# uno.net
KiCad netlist of a schematic drawn in EAGLE
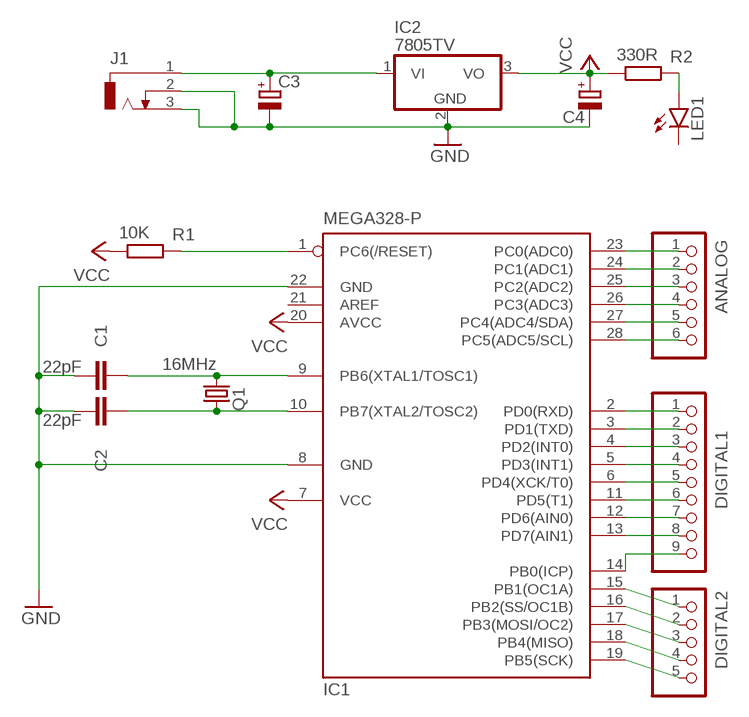
[diagram p0: schematic, sheet 1]

(export (version "E")
  (design (tool "Eeschema 10.0.6"))
  (components
    (comp (ref "ANALOG")
      (value "PINHD-1X6")
      (footprint "eagle-import:1X06")
      (libsource (lib "eagle-import") (part "PINHD-1X6"))
    )
    (comp (ref "C1")
      (value "22pF")
      (footprint "eagle-import:C025-024X044")
      (libsource (lib "eagle-import") (part "C-EU025-024X044"))
    )
    (comp (ref "C2")
      (value "22pF")
      (footprint "eagle-import:C025-024X044")
      (libsource (lib "eagle-import") (part "C-EU025-024X044"))
    )
    (comp (ref "C3")
      (value "CPOL-EUE2.5-6")
      (footprint "eagle-import:E2,5-6")
      (libsource (lib "eagle-import") (part "CPOL-EUE2.5-6"))
    )
    (comp (ref "C4")
      (value "CPOL-EUE2.5-6")
      (footprint "eagle-import:E2,5-6")
      (libsource (lib "eagle-import") (part "CPOL-EUE2.5-6"))
    )
    (comp (ref "DIGITAL1")
      (value "PINHD-1X9")
      (footprint "eagle-import:1X09")
      (libsource (lib "eagle-import") (part "PINHD-1X9"))
    )
    (comp (ref "DIGITAL2")
      (value "PINHD-1X5")
      (footprint "eagle-import:1X05")
      (libsource (lib "eagle-import") (part "PINHD-1X5"))
    )
    (comp (ref "IC1")
      (value "MEGA328-P")
      (footprint "eagle-import:DIL28-3")
      (libsource (lib "eagle-import") (part "MEGA8-P"))
    )
    (comp (ref "IC2")
      (value "7805TV")
      (footprint "eagle-import:TO220V")
      (libsource (lib "eagle-import") (part "78TV05"))
    )
    (comp (ref "J1")
      (value "DCJ0303")
      (footprint "eagle-import:DCJ0303")
      (libsource (lib "eagle-import") (part "DCJ0303"))
    )
    (comp (ref "LED1")
      (value "LED3MM")
      (footprint "eagle-import:LED3MM")
      (libsource (lib "eagle-import") (part "LED3MM"))
    )
    (comp (ref "Q1")
      (value "16MHz")
      (footprint "eagle-import:HC49U70")
      (libsource (lib "eagle-import") (part "CRYSTALHC49U70"))
    )
    (comp (ref "R1")
      (value "10K")
      (footprint "eagle-import:0207_10")
      (libsource (lib "eagle-import") (part "R-EU_0207/10"))
    )
    (comp (ref "R2")
      (value "330R")
      (footprint "eagle-import:0207_10")
      (libsource (lib "eagle-import") (part "R-EU_0207/10"))
    )
  )
  (nets
    (net (code "1") (name "GND") (class "Default")
      (node (ref "C1") (pin "1") (pinfunction "1_1") (pintype "passive"))
      (node (ref "C2") (pin "1") (pinfunction "1_1") (pintype "passive"))
      (node (ref "C3") (pin "-") (pinfunction "-_-") (pintype "passive"))
      (node (ref "C4") (pin "-") (pinfunction "-_-") (pintype "passive"))
      (node (ref "IC1") (pin "22") (pinfunction "GND_22") (pintype "power_in"))
      (node (ref "IC1") (pin "8") (pinfunction "GND_8") (pintype "power_in"))
      (node (ref "IC2") (pin "2") (pinfunction "GND_2") (pintype "passive"))
      (node (ref "J1") (pin "2") (pinfunction "2_2") (pintype "passive"))
      (node (ref "J1") (pin "3") (pinfunction "3_3") (pintype "passive"))
    )
    (net (code "2") (name "Net-(IC1-PB0(ICP))") (class "Default")
      (node (ref "DIGITAL1") (pin "9") (pinfunction "9_9") (pintype "passive"))
      (node (ref "IC1") (pin "14") (pinfunction "PB0(ICP)_14") (pintype "bidirectional"))
    )
    (net (code "3") (name "Net-(IC1-PB1(OC1A))") (class "Default")
      (node (ref "DIGITAL2") (pin "1") (pinfunction "1_1") (pintype "passive"))
      (node (ref "IC1") (pin "15") (pinfunction "PB1(OC1A)_15") (pintype "bidirectional"))
    )
    (net (code "4") (name "Net-(IC1-PB2(SS{slash}OC1B))") (class "Default")
      (node (ref "DIGITAL2") (pin "2") (pinfunction "2_2") (pintype "passive"))
      (node (ref "IC1") (pin "16") (pinfunction "PB2(SS/OC1B)_16") (pintype "bidirectional"))
    )
    (net (code "5") (name "Net-(IC1-PB3(MOSI{slash}OC2))") (class "Default")
      (node (ref "DIGITAL2") (pin "3") (pinfunction "3_3") (pintype "passive"))
      (node (ref "IC1") (pin "17") (pinfunction "PB3(MOSI/OC2)_17") (pintype "bidirectional"))
    )
    (net (code "6") (name "Net-(IC1-PB4(MISO))") (class "Default")
      (node (ref "DIGITAL2") (pin "4") (pinfunction "4_4") (pintype "passive"))
      (node (ref "IC1") (pin "18") (pinfunction "PB4(MISO)_18") (pintype "bidirectional"))
    )
    (net (code "7") (name "Net-(IC1-PB5(SCK))") (class "Default")
      (node (ref "DIGITAL2") (pin "5") (pinfunction "5_5") (pintype "passive"))
      (node (ref "IC1") (pin "19") (pinfunction "PB5(SCK)_19") (pintype "bidirectional"))
    )
    (net (code "8") (name "Net-(IC1-PB6(XTAL1{slash}TOSC1))") (class "Default")
      (node (ref "C1") (pin "2") (pinfunction "2_2") (pintype "passive"))
      (node (ref "IC1") (pin "9") (pinfunction "PB6(XTAL1/TOSC1)_9") (pintype "bidirectional"))
      (node (ref "Q1") (pin "2") (pinfunction "2_2") (pintype "passive"))
    )
    (net (code "9") (name "Net-(IC1-PB7(XTAL2{slash}TOSC2))") (class "Default")
      (node (ref "C2") (pin "2") (pinfunction "2_2") (pintype "passive"))
      (node (ref "IC1") (pin "10") (pinfunction "PB7(XTAL2/TOSC2)_10") (pintype "bidirectional"))
      (node (ref "Q1") (pin "1") (pinfunction "1_1") (pintype "passive"))
    )
    (net (code "10") (name "Net-(IC1-PC0(ADC0))") (class "Default")
      (node (ref "ANALOG") (pin "1") (pinfunction "1_1") (pintype "passive"))
      (node (ref "IC1") (pin "23") (pinfunction "PC0(ADC0)_23") (pintype "bidirectional"))
    )
    (net (code "11") (name "Net-(IC1-PC1(ADC1))") (class "Default")
      (node (ref "ANALOG") (pin "2") (pinfunction "2_2") (pintype "passive"))
      (node (ref "IC1") (pin "24") (pinfunction "PC1(ADC1)_24") (pintype "bidirectional"))
    )
    (net (code "12") (name "Net-(IC1-PC2(ADC2))") (class "Default")
      (node (ref "ANALOG") (pin "3") (pinfunction "3_3") (pintype "passive"))
      (node (ref "IC1") (pin "25") (pinfunction "PC2(ADC2)_25") (pintype "bidirectional"))
    )
    (net (code "13") (name "Net-(IC1-PC3(ADC3))") (class "Default")
      (node (ref "ANALOG") (pin "4") (pinfunction "4_4") (pintype "passive"))
      (node (ref "IC1") (pin "26") (pinfunction "PC3(ADC3)_26") (pintype "bidirectional"))
    )
    (net (code "14") (name "Net-(IC1-PC4(ADC4{slash}SDA))") (class "Default")
      (node (ref "ANALOG") (pin "5") (pinfunction "5_5") (pintype "passive"))
      (node (ref "IC1") (pin "27") (pinfunction "PC4(ADC4/SDA)_27") (pintype "bidirectional"))
    )
    (net (code "15") (name "Net-(IC1-PC5(ADC5{slash}SCL))") (class "Default")
      (node (ref "ANALOG") (pin "6") (pinfunction "6_6") (pintype "passive"))
      (node (ref "IC1") (pin "28") (pinfunction "PC5(ADC5/SCL)_28") (pintype "bidirectional"))
    )
    (net (code "16") (name "Net-(IC1-PC6({slash}RESET))") (class "Default")
      (node (ref "IC1") (pin "1") (pinfunction "PC6(/RESET)_1") (pintype "bidirectional"))
      (node (ref "R1") (pin "2") (pinfunction "2_2") (pintype "passive"))
    )
    (net (code "17") (name "Net-(IC1-PD0(RXD))") (class "Default")
      (node (ref "DIGITAL1") (pin "1") (pinfunction "1_1") (pintype "passive"))
      (node (ref "IC1") (pin "2") (pinfunction "PD0(RXD)_2") (pintype "bidirectional"))
    )
    (net (code "18") (name "Net-(IC1-PD1(TXD))") (class "Default")
      (node (ref "DIGITAL1") (pin "2") (pinfunction "2_2") (pintype "passive"))
      (node (ref "IC1") (pin "3") (pinfunction "PD1(TXD)_3") (pintype "bidirectional"))
    )
    (net (code "19") (name "Net-(IC1-PD2(INT0))") (class "Default")
      (node (ref "DIGITAL1") (pin "3") (pinfunction "3_3") (pintype "passive"))
      (node (ref "IC1") (pin "4") (pinfunction "PD2(INT0)_4") (pintype "bidirectional"))
    )
    (net (code "20") (name "Net-(IC1-PD3(INT1))") (class "Default")
      (node (ref "DIGITAL1") (pin "4") (pinfunction "4_4") (pintype "passive"))
      (node (ref "IC1") (pin "5") (pinfunction "PD3(INT1)_5") (pintype "bidirectional"))
    )
    (net (code "21") (name "Net-(IC1-PD4(XCK{slash}T0))") (class "Default")
      (node (ref "DIGITAL1") (pin "5") (pinfunction "5_5") (pintype "passive"))
      (node (ref "IC1") (pin "6") (pinfunction "PD4(XCK/T0)_6") (pintype "bidirectional"))
    )
    (net (code "22") (name "Net-(IC1-PD5(T1))") (class "Default")
      (node (ref "DIGITAL1") (pin "6") (pinfunction "6_6") (pintype "passive"))
      (node (ref "IC1") (pin "11") (pinfunction "PD5(T1)_11") (pintype "bidirectional"))
    )
    (net (code "23") (name "Net-(IC1-PD6(AIN0))") (class "Default")
      (node (ref "DIGITAL1") (pin "7") (pinfunction "7_7") (pintype "passive"))
      (node (ref "IC1") (pin "12") (pinfunction "PD6(AIN0)_12") (pintype "bidirectional"))
    )
    (net (code "24") (name "Net-(IC1-PD7(AIN1))") (class "Default")
      (node (ref "DIGITAL1") (pin "8") (pinfunction "8_8") (pintype "passive"))
      (node (ref "IC1") (pin "13") (pinfunction "PD7(AIN1)_13") (pintype "bidirectional"))
    )
    (net (code "25") (name "Net-(IC2-VI)") (class "Default")
      (node (ref "C3") (pin "+") (pinfunction "+_+") (pintype "passive"))
      (node (ref "IC2") (pin "1") (pinfunction "VI_1") (pintype "input"))
      (node (ref "J1") (pin "1") (pinfunction "1_1") (pintype "passive"))
    )
    (net (code "26") (name "Net-(LED1-PadA)") (class "Default")
      (node (ref "LED1") (pin "A") (pinfunction "A_A") (pintype "passive"))
      (node (ref "R2") (pin "2") (pinfunction "2_2") (pintype "passive"))
    )
    (net (code "27") (name "VCC") (class "Default")
      (node (ref "C4") (pin "+") (pinfunction "+_+") (pintype "passive"))
      (node (ref "IC1") (pin "20") (pinfunction "AVCC_20") (pintype "power_in"))
      (node (ref "IC1") (pin "7") (pinfunction "VCC_7") (pintype "power_in"))
      (node (ref "IC2") (pin "3") (pinfunction "VO_3") (pintype "passive"))
      (node (ref "R1") (pin "1") (pinfunction "1_1") (pintype "passive"))
      (node (ref "R2") (pin "1") (pinfunction "1_1") (pintype "passive"))
    )
    (net (code "28") (name "unconnected-(IC1-AREF-Pad21)") (class "Default")
      (node (ref "IC1") (pin "21") (pinfunction "AREF_21") (pintype "passive"))
    )
    (net (code "29") (name "unconnected-(LED1-C-PadK)") (class "Default")
      (node (ref "LED1") (pin "K") (pinfunction "C_K") (pintype "passive"))
    )
  )
)
